# supply_unit.net
KiCad netlist of a schematic drawn in Altium Designer
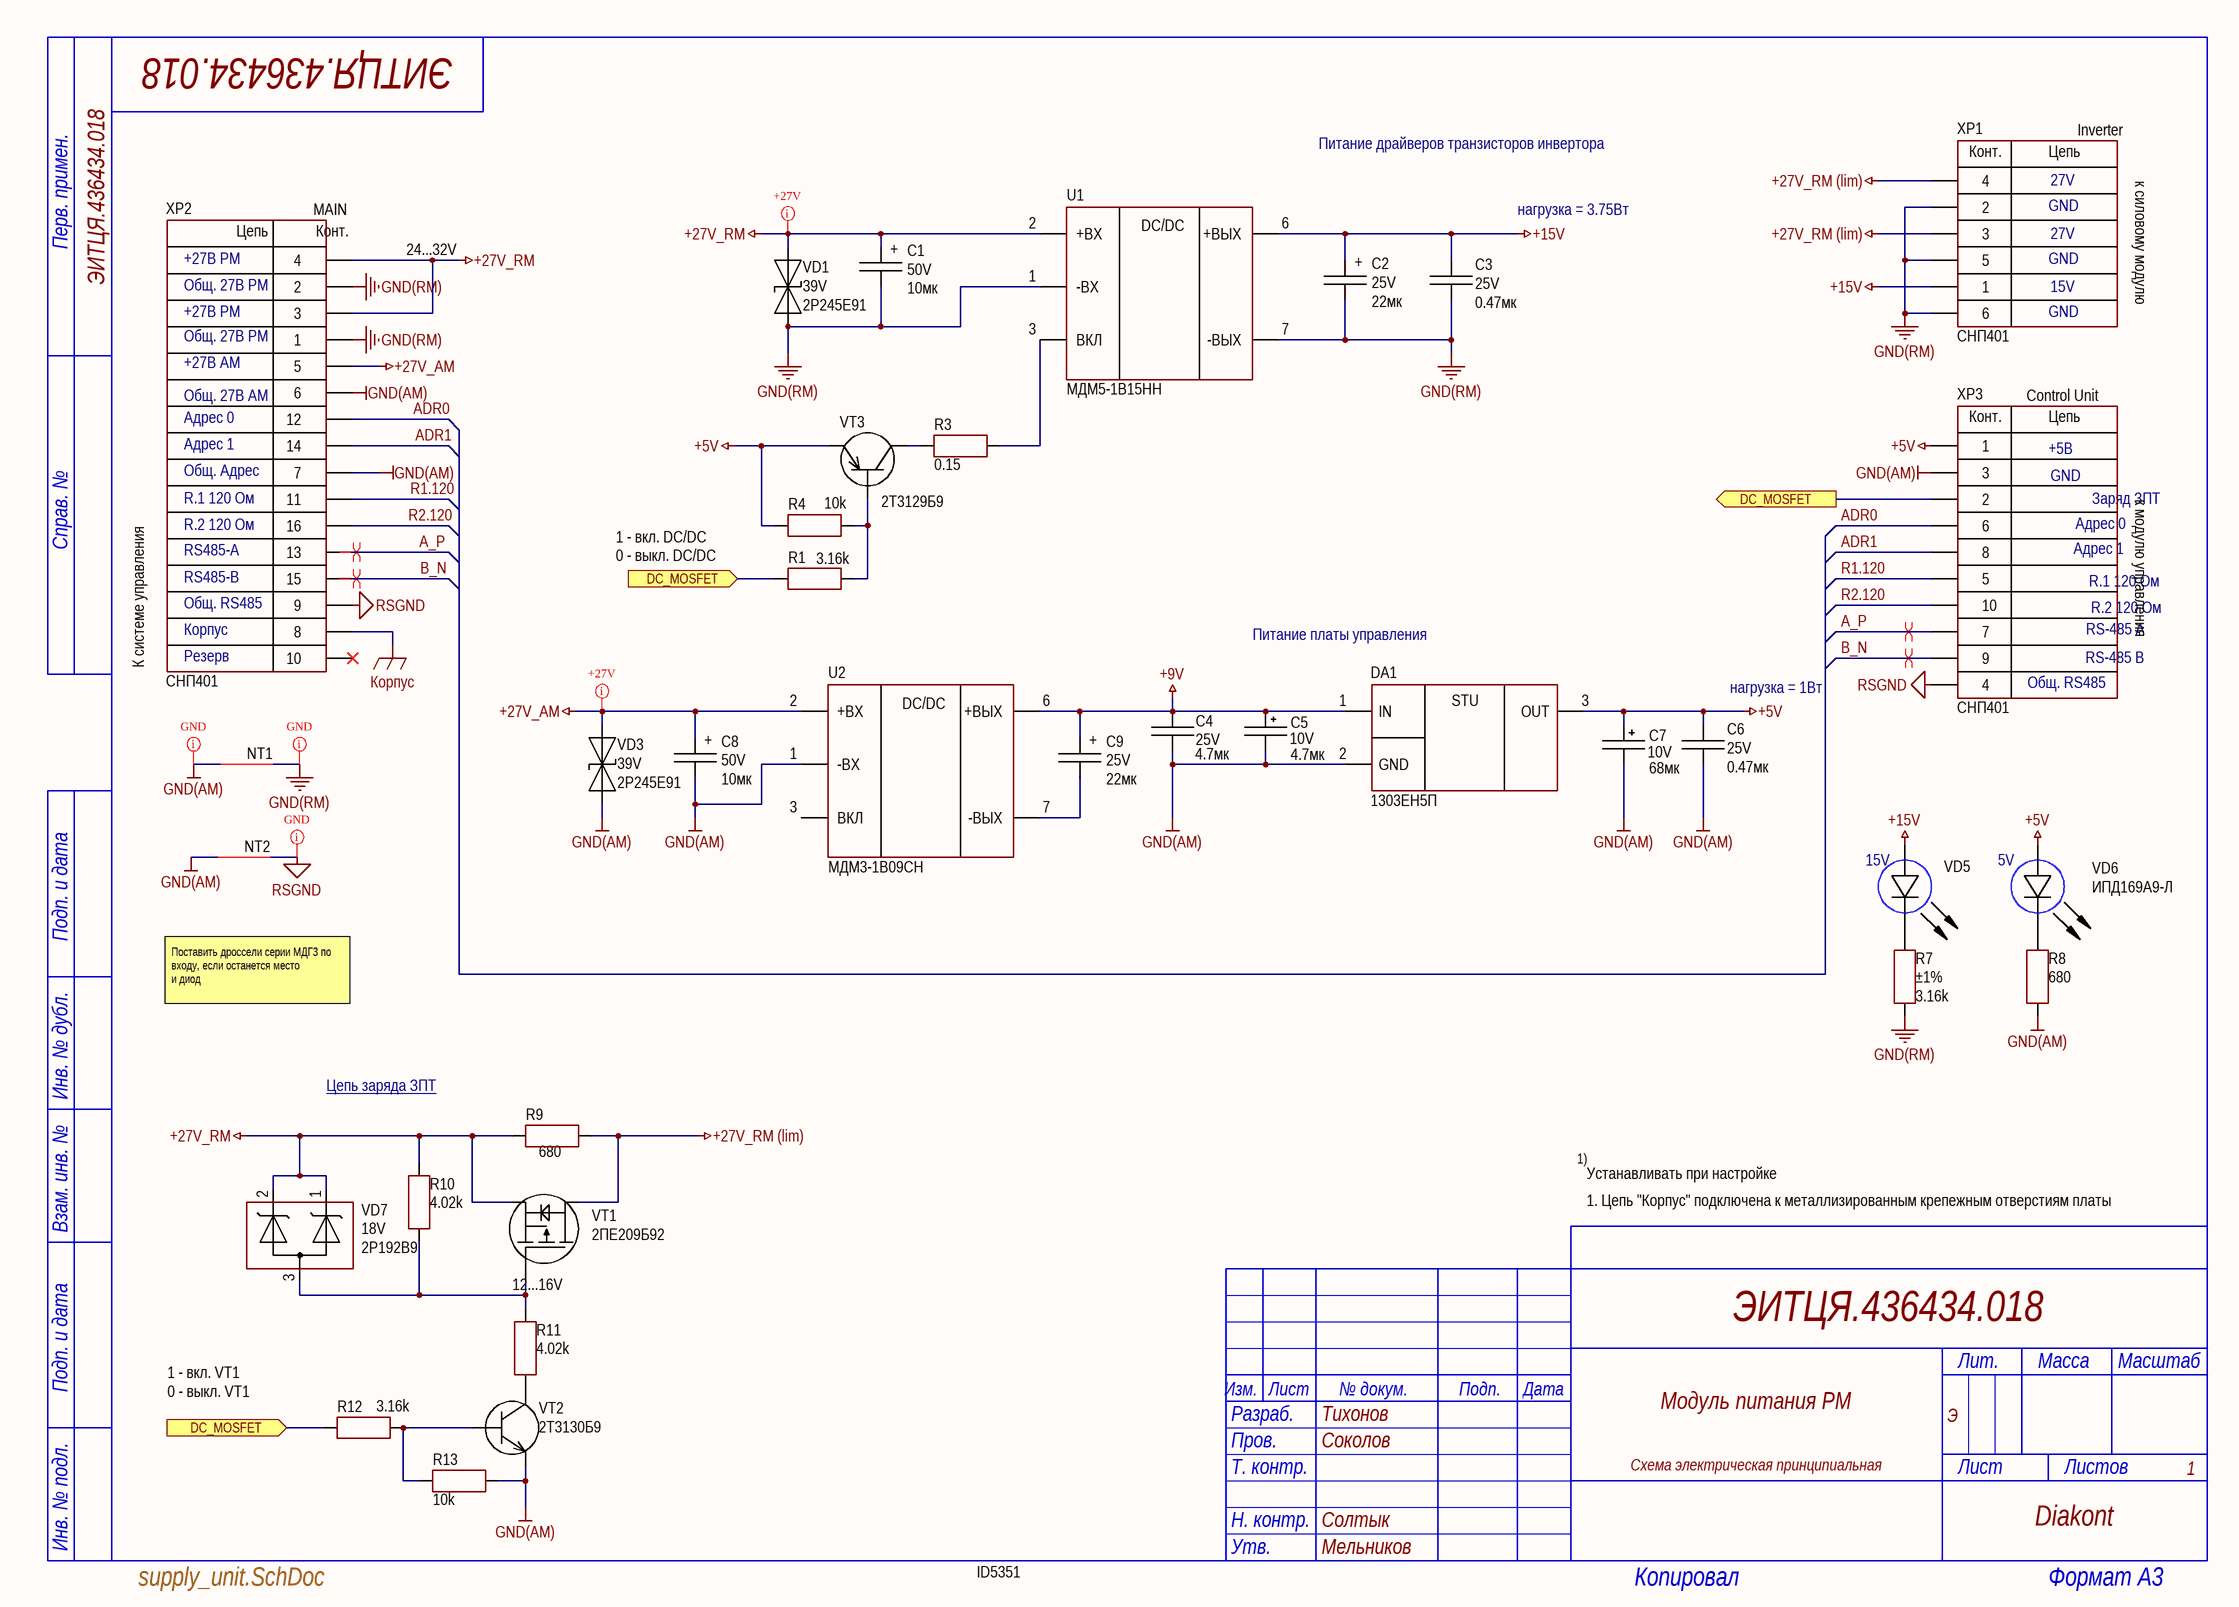
[diagram p0: supply_unit.SchDoc]

(export (version "E")
  (design (tool "Eeschema 10.0.6"))
  (components
    (comp (ref "C1")
      (value "10мк")
      (footprint "StandardCase:CAP: TANTAL-E")
      (fields
        (field (name "MANUFACTURER") "Элеконд")
        (field (name "PARTNUMBER") "К53-68 \"E\"-50 В-10мкф ±10%")
        (field (name "VALUEMANUFACTURERPARTNUMBER") "Tantalum capacitor, 10мк, 50V, ±10%, 0.7 Ом, case E, -60...+125°C")
        (field (name "POLARITY") "+")
        (field (name "VOLTAGE") "50V")
      )
      (libsource (lib "Capacitor") (part "Tantal_E"))
    )
    (comp (ref "C2")
      (value "22мк")
      (footprint "StandardCase:CAP: TANTAL-D")
      (fields
        (field (name "MANUFACTURER") "Элеконд")
        (field (name "PARTNUMBER") "К53-68 \"D\"-25 В-22мкф ±10%")
        (field (name "VALUEMANUFACTURERPARTNUMBER") "Tantalum capacitor, 22мк, 25V, ±10%, 0.7 Ом, case D, -60...+125°C")
        (field (name "POLARITY") "+")
        (field (name "VOLTAGE") "25V")
      )
      (libsource (lib "Capacitor") (part "Tantal_E"))
    )
    (comp (ref "C3")
      (value "0.47мк")
      (footprint "StandardCase:CAP: 1206")
      (fields
        (field (name "MANUFACTURER") "Монолит")
        (field (name "PARTNUMBER") "К10-84в-3216М-25В-0,47 мкФ ±10%-Н90-N-A")
        (field (name "VALUEMANUFACTURERPARTNUMBER") "Ceramic capacitor, 0.47мк, Н90, ±10%, 25V, 1206 (3216M), ")
        (field (name "VOLTAGE") "25V")
      )
      (libsource (lib "Capacitor") (part "Ceramic_0603"))
    )
    (comp (ref "C4")
      (value "4.7мк")
      (footprint "StandardCase:CAP: 1812")
      (fields
        (field (name "MANUFACTURER") "Монолит")
        (field (name "PARTNUMBER") "К10-84в-4532М-25В-4,7 мкФ +80/-20%-Н90-N-A")
        (field (name "VALUEMANUFACTURERPARTNUMBER") "Ceramic capacitor, 4.7мк, H90, +80 -20%, 25V, 1812 (4532М) (4.5x3.2), -55...+125°C")
        (field (name "VOLTAGE") "25V")
      )
      (libsource (lib "Capacitor") (part "Ceramic_1812"))
    )
    (comp (ref "C5")
      (value "4.7мк")
      (footprint "StandardCase:CAP: TANTAL-A")
      (fields
        (field (name "MANUFACTURER") "Элеконд")
        (field (name "PARTNUMBER") "К53-68 \"А\"-10 В-4.7 мкф")
        (field (name "VALUEMANUFACTURERPARTNUMBER") "Tantalum capacitor, 4.7мк, 10V, ±10%, 2Ohm, case A (3216), -55...+125°C")
        (field (name "VOLTAGE") "10V")
      )
      (libsource (lib "Capacitor") (part "Tantal_A"))
    )
    (comp (ref "C6")
      (value "0.47мк")
      (footprint "StandardCase:CAP: 1206")
      (fields
        (field (name "MANUFACTURER") "Монолит")
        (field (name "PARTNUMBER") "К10-84в-3216М-25В-0,47 мкФ ±10%-Н90-N-A")
        (field (name "VALUEMANUFACTURERPARTNUMBER") "Ceramic capacitor, 0.47мк, Н90, ±10%, 25V, 1206 (3216M), ")
        (field (name "VOLTAGE") "25V")
      )
      (libsource (lib "Capacitor") (part "Ceramic_0603"))
    )
    (comp (ref "C7")
      (value "68мк")
      (footprint "StandardCase:CAP: TANTAL-C")
      (fields
        (field (name "MANUFACTURER") "Элеконд")
        (field (name "PARTNUMBER") "К53-68 \"C\"-10 В-68 мкф")
        (field (name "VALUEMANUFACTURERPARTNUMBER") "Tantalum capacitor, 68мк, 10V, ±10%, 1.2 - 1.8Ohm, case C, -55...+125°C")
        (field (name "VOLTAGE") "10V")
      )
      (libsource (lib "Capacitor") (part "Tantal_A"))
    )
    (comp (ref "C8")
      (value "10мк")
      (footprint "StandardCase:CAP: TANTAL-E")
      (fields
        (field (name "MANUFACTURER") "Элеконд")
        (field (name "PARTNUMBER") "К53-68 \"E\"-50 В-10мкф ±10%")
        (field (name "VALUEMANUFACTURERPARTNUMBER") "Tantalum capacitor, 10мк, 50V, ±10%, 0.7 Ом, case E, -60...+125°C")
        (field (name "POLARITY") "+")
        (field (name "VOLTAGE") "50V")
      )
      (libsource (lib "Capacitor") (part "Tantal_E"))
    )
    (comp (ref "C9")
      (value "22мк")
      (footprint "StandardCase:CAP: TANTAL-D")
      (fields
        (field (name "MANUFACTURER") "Элеконд")
        (field (name "PARTNUMBER") "К53-68 \"D\"-25 В-22мкф ±10%")
        (field (name "VALUEMANUFACTURERPARTNUMBER") "Tantalum capacitor, 22мк, 25V, ±10%, 0.7 Ом, case D, -60...+125°C")
        (field (name "POLARITY") "+")
        (field (name "VOLTAGE") "25V")
      )
      (libsource (lib "Capacitor") (part "Tantal_E"))
    )
    (comp (ref "DA1")
      (value "~")
      (footprint "TO220 (КТ-28А)")
      (description "Linear voltage regulator 5V")
      (fields
        (field (name "MANUFACTURER") "ELTOM")
        (field (name "VALUEMANUFACTURERPARTNUMBER") "Linear voltage regulator, input 5.8...16V, 0.6V, output 5V, 5A, -60...+125°C, КТ28А (TO-220)")
        (field (name "PARTNUMBER") "1303ЕН5П")
      )
      (libsource (lib "IC. Power supply") (part "1303ЕН5П"))
    )
    (comp (ref "NT1")
      (value "~")
      (footprint "CustomCase:NetTie_0603")
      (libsource (lib "Connector") (part "NetTie"))
    )
    (comp (ref "NT2")
      (value "~")
      (footprint "CustomCase:NetTie_0603")
      (libsource (lib "Connector") (part "NetTie"))
    )
    (comp (ref "R1")
      (value "3.16k")
      (footprint "RES: 0603P")
      (fields
        (field (name "MANUFACTURER") "ОАО Ресурс")
        (field (name "PARTNUMBER") "Р1-12-0,1ум.-3.16~кОм ±1%-М ШКАБ.434110.002 ТУ")
        (field (name "VALUEMANUFACTURERPARTNUMBER") "Resistor film, 3.16k, ±1%, 0603, 0.1W, -55...+125°C")
      )
      (libsource (lib "") (part "Resistor_0603_1"))
    )
    (comp (ref "R3")
      (value "0.15")
      (footprint "RES: 0603P")
      (fields
        (field (name "MANUFACTURER") "ОАО Ресурс")
        (field (name "PARTNUMBER") "Р1-12-0,1ум.-0.15~Ом ±20%-М ШКАБ.434110.002 ТУ")
        (field (name "VALUEMANUFACTURERPARTNUMBER") "Resistor film, 0.15, ±20%, 0603, 0.1W, -55...+125°C")
      )
      (libsource (lib "Resistor") (part "Resistor_0603"))
    )
    (comp (ref "R4")
      (value "10k")
      (footprint "RES: 0603P")
      (fields
        (field (name "MANUFACTURER") "ОАО Ресурс")
        (field (name "PARTNUMBER") "Р1-12-0,1ум.-10~кОм ±5%-М ШКАБ.434110.002 ТУ")
        (field (name "VALUEMANUFACTURERPARTNUMBER") "Resistor film, 10k, ±5%, 0603, 0.1W, -55...+125°C")
      )
      (libsource (lib "") (part "Resistor_0603_2"))
    )
    (comp (ref "R7")
      (value "3.16k")
      (footprint "RES: 0603P")
      (fields
        (field (name "MANUFACTURER") "ОАО Ресурс")
        (field (name "PARTNUMBER") "Р1-12-0,1ум.-3.16~кОм ±1%-М ШКАБ.434110.002 ТУ")
        (field (name "VALUEMANUFACTURERPARTNUMBER") "Resistor film, 3.16k, ±1%, 0603, 0.1W, -55...+125°C")
        (field (name "TOLERANCE") "±1%")
      )
      (libsource (lib "") (part "Resistor_0603_2"))
    )
    (comp (ref "R8")
      (value "680")
      (footprint "RES: 0603P")
      (fields
        (field (name "MANUFACTURER") "ОАО Ресурс")
        (field (name "PARTNUMBER") "Р1-12-0,1ум.-680~Ом ±5%-М ШКАБ.434110.002 ТУ")
        (field (name "VALUEMANUFACTURERPARTNUMBER") "Resistor film, 680, ±5%, 0603, 0.1W, -55...+125°C")
      )
      (libsource (lib "") (part "Resistor_0603_1"))
    )
    (comp (ref "R9")
      (value "680")
      (footprint "StandardCase:RES: 0805P")
      (fields
        (field (name "MANUFACTURER") "Ресурс")
        (field (name "PARTNUMBER") "Р1-12-0,125-680 Ом ±5%-М ШКАБ.434110.002 ТУ")
        (field (name "VALUEMANUFACTURERPARTNUMBER") "Resistor film, 680, ±5%, 0805, 0.125W, ")
      )
      (libsource (lib "Resistor") (part "Resistor_0805"))
    )
    (comp (ref "R10")
      (value "4.02k")
      (footprint "RES: 0805P")
      (fields
        (field (name "MANUFACTURER") "ОАО Ресурс")
        (field (name "PARTNUMBER") "Р1-12-0,1ум.-4.02~кОм ±1%-М ШКАБ.434110.002 ТУ")
        (field (name "VALUEMANUFACTURERPARTNUMBER") "Resistor film, 4.02k, ±1%, 0805, 0.125W, -55...+125°C")
      )
      (libsource (lib "") (part "Resistor_0603_1"))
    )
    (comp (ref "R11")
      (value "4.02k")
      (footprint "RES: 0805P")
      (fields
        (field (name "MANUFACTURER") "ОАО Ресурс")
        (field (name "PARTNUMBER") "Р1-12-0,1ум.-4.02~кОм ±1%-М ШКАБ.434110.002 ТУ")
        (field (name "VALUEMANUFACTURERPARTNUMBER") "Resistor film, 4.02k, ±1%, 0805, 0.125W, -55...+125°C")
      )
      (libsource (lib "") (part "Resistor_0603_1"))
    )
    (comp (ref "R12")
      (value "3.16k")
      (footprint "RES: 0603P")
      (fields
        (field (name "MANUFACTURER") "ОАО Ресурс")
        (field (name "PARTNUMBER") "Р1-12-0,1ум.-3.16~кОм ±1%-М ШКАБ.434110.002 ТУ")
        (field (name "VALUEMANUFACTURERPARTNUMBER") "Resistor film, 3.16k, ±1%, 0603, 0.1W, -55...+125°C")
      )
      (libsource (lib "Resistor") (part "Resistor_0603"))
    )
    (comp (ref "R13")
      (value "10k")
      (footprint "RES: 0603P")
      (fields
        (field (name "MANUFACTURER") "ОАО Ресурс")
        (field (name "PARTNUMBER") "Р1-12-0,1ум.-10~кОм ±5%-М ШКАБ.434110.002 ТУ")
        (field (name "VALUEMANUFACTURERPARTNUMBER") "Resistor film, 10k, ±5%, 0603, 0.1W, -55...+125°C")
      )
      (libsource (lib "") (part "Resistor_0603_3"))
    )
    (comp (ref "U1")
      (value "~")
      (footprint "StandardCase:SIP-8")
      (description "DC/DC converter")
      (fields
        (field (name "MANUFACTURER") "Aedon")
        (field (name "VALUEMANUFACTURERPARTNUMBER") "DC/DC converter, isolator, 15V 1.5A, -40...+105°C, SIP-8")
        (field (name "PARTNUMBER") "МДМ5-1В15НН")
      )
      (libsource (lib "Module") (part "МДМ3-1В09СН"))
    )
    (comp (ref "U2")
      (value "~")
      (footprint "StandardCase:SIP-8")
      (description "DC/DC converter")
      (fields
        (field (name "MANUFACTURER") "Aedon")
        (field (name "VALUEMANUFACTURERPARTNUMBER") "DC/DC converter, isolator, 9V 900mA, -40...+105°C, SIP-8")
        (field (name "PARTNUMBER") "МДМ3-1В09СН")
      )
      (libsource (lib "Module") (part "МДМ3-1В09СН"))
    )
    (comp (ref "VD1")
      (value "~")
      (footprint "StandardCase:DIODE: SMB")
      (fields
        (field (name "MANUFACTURER") "НЗПП")
        (field (name "VALUEMANUFACTURERPARTNUMBER") "Zener diode, 39V, 8A, 0.9V, , SMB(КД-42), ")
        (field (name "VOLTAGE") "39V")
        (field (name "PARTNUMBER") "2Р245Е91")
      )
      (libsource (lib "Diode") (part "TVS_single"))
    )
    (comp (ref "VD3")
      (value "~")
      (footprint "StandardCase:DIODE: SMB")
      (fields
        (field (name "MANUFACTURER") "НЗПП")
        (field (name "VALUEMANUFACTURERPARTNUMBER") "Zener diode, 39V, 8A, 0.9V, , SMB(КД-42), ")
        (field (name "VOLTAGE") "39V")
        (field (name "PARTNUMBER") "2Р245Е91")
      )
      (libsource (lib "Diode") (part "TVS_single"))
    )
    (comp (ref "VD5")
      (value "~")
      (footprint "StandardCase:LED: 0603G")
      (fields
        (field (name "MANUFACTURER") "Протон")
        (field (name "VALUEMANUFACTURERPARTNUMBER") "LED, 20mA max, 2.1V typ, 1608, -55...+150°C")
        (field (name "PARTNUMBER") "ИПД169А9-Л")
        (field (name "COMMENTTEXT") "15V")
      )
      (libsource (lib "Diode") (part "LED_single"))
    )
    (comp (ref "VD6")
      (value "~")
      (footprint "StandardCase:LED: 0603G")
      (fields
        (field (name "MANUFACTURER") "Протон")
        (field (name "VALUEMANUFACTURERPARTNUMBER") "LED, 20mA max, 2.1V typ, 1608, -55...+150°C")
        (field (name "PARTNUMBER") "ИПД169А9-Л")
        (field (name "COMMENTTEXT") "5V")
      )
      (libsource (lib "Diode") (part "LED_single"))
    )
    (comp (ref "VD7")
      (value "~")
      (footprint "StandardCase:SOT23")
      (fields
        (field (name "MANUFACTURER") "КРИП")
        (field (name "VALUEMANUFACTURERPARTNUMBER") "TVS diode, 18V, 1A, , , SOT-23, -55...+150°C")
        (field (name "VOLTAGE") "18V")
        (field (name "PARTNUMBER") "2Р192В9")
      )
      (libsource (lib "Diode") (part "TVS_array_var2"))
    )
    (comp (ref "VT1")
      (value "~")
      (footprint "StandardCase:DPAK")
      (fields (field (name "MANUFACTURER") "Ангстрем") (field (name "PARTNUMBER") "2ПЕ209Б92"))
      (libsource (lib "Transistor") (part "MOSFET_P_132"))
    )
    (comp (ref "VT2")
      (value "~")
      (footprint "SOT23")
      (fields
        (field (name "MANUFACTURER") "ООО НПК Далекс")
        (field (name "VALUEMANUFACTURERPARTNUMBER") "NPN transistor, 30V, 100mA, , 300mW, 0.7V, 500, SOT-23 (КТ-46), -55...+125°C")
        (field (name "PARTNUMBER") "2Т3130Б9")
      )
      (libsource (lib "Transistor") (part "BJT_NPN_132"))
    )
    (comp (ref "VT3")
      (value "~")
      (footprint "StandardCase:SOT23")
      (fields
        (field (name "VALUEMANUFACTURERPARTNUMBER") "NPN transistor, 40V, 100mA, , 200mW, 1.3V, 220, SOT-23 (КТ-46), ")
        (field (name "PARTNUMBER") "2Т3129Б9")
      )
      (libsource (lib "Transistor") (part "BJT_PNP_123"))
    )
    (comp (ref "XP1")
      (value "~")
      (footprint "CON: M80-5000605")
      (description "вилка на плату")
      (fields
        (field (name "MANUFACTURER") "Электроделать")
        (field (name "VALUEMANUFACTURERPARTNUMBER") "Вилка, 6pin, 2mm, 120VAC, 1.5A")
        (field (name "COMMENTTEXT") "СНП401")
      )
      (libsource (lib "Connector") (part "M80-5000605 Harwin"))
    )
    (comp (ref "XP2")
      (value "~")
      (footprint "CustomCase:CON: M80-5001605")
      (description "вилка на плату")
      (fields
        (field (name "MANUFACTURER") "Электродеталь")
        (field (name "VALUEMANUFACTURERPARTNUMBER") ", 16pin, 2mm, 120VAC, 1.5A")
        (field (name "COMMENTTEXT") "СНП401")
      )
      (libsource (lib "Connector") (part "M80-5001205 Harwin_1"))
    )
    (comp (ref "XP3")
      (value "~")
      (footprint "CON: M80-5001005")
      (description "вилка на плату")
      (fields
        (field (name "MANUFACTURER") "Электродеталь")
        (field (name "VALUEMANUFACTURERPARTNUMBER") "Вилка, 10pin, 2mm, 100V, 1.5A")
        (field (name "COMMENTTEXT") "СНП401")
      )
      (libsource (lib "Connector") (part "M80-5001005 Harwin"))
    )
  )
  (nets
    (net (code "1") (name "+5V") (class "Default")
      (node (ref "C6") (pin "2") (pinfunction "2_2") (pintype "passive"))
      (node (ref "C7") (pin "1") (pinfunction "1_1") (pintype "power_in"))
      (node (ref "DA1") (pin "3") (pinfunction "OUT_3") (pintype "power_in"))
      (node (ref "R4") (pin "1") (pinfunction "1_1") (pintype "passive"))
      (node (ref "VD6") (pin "1") (pinfunction "A_1") (pintype "passive"))
      (node (ref "VT3") (pin "2") (pinfunction "E_2") (pintype "passive"))
      (node (ref "XP3") (pin "1") (pinfunction "1_1") (pintype "passive"))
    )
    (net (code "2") (name "+9V") (class "Default")
      (node (ref "C4") (pin "2") (pinfunction "2_2") (pintype "passive"))
      (node (ref "C5") (pin "1") (pinfunction "1_1") (pintype "power_in"))
      (node (ref "C9") (pin "2") (pinfunction "2_2") (pintype "power_in"))
      (node (ref "DA1") (pin "1") (pinfunction "IN_1") (pintype "power_in"))
      (node (ref "U2") (pin "6") (pinfunction "+ВЫХ_6") (pintype "power_in"))
    )
    (net (code "3") (name "+15V") (class "Default")
      (node (ref "C2") (pin "2") (pinfunction "2_2") (pintype "power_in"))
      (node (ref "C3") (pin "2") (pinfunction "2_2") (pintype "passive"))
      (node (ref "U1") (pin "6") (pinfunction "+ВЫХ_6") (pintype "power_in"))
      (node (ref "VD5") (pin "1") (pinfunction "A_1") (pintype "passive"))
      (node (ref "XP1") (pin "1") (pinfunction "1_1") (pintype "passive"))
    )
    (net (code "4") (name "+27V_AM") (class "Default")
      (node (ref "C8") (pin "2") (pinfunction "2_2") (pintype "power_in"))
      (node (ref "U2") (pin "2") (pinfunction "+ВХ_2") (pintype "power_in"))
      (node (ref "VD3") (pin "2") (pinfunction "C_2") (pintype "passive"))
      (node (ref "XP2") (pin "5") (pinfunction "5_5") (pintype "passive"))
    )
    (net (code "5") (name "+27V_RM") (class "Default")
      (node (ref "C1") (pin "2") (pinfunction "2_2") (pintype "power_in"))
      (node (ref "R10") (pin "1") (pinfunction "1_1") (pintype "passive"))
      (node (ref "R9") (pin "1") (pinfunction "1_1") (pintype "passive"))
      (node (ref "U1") (pin "2") (pinfunction "+ВХ_2") (pintype "power_in"))
      (node (ref "VD1") (pin "2") (pinfunction "C_2") (pintype "passive"))
      (node (ref "VD7") (pin "1") (pinfunction "K1_1") (pintype "passive"))
      (node (ref "VD7") (pin "2") (pinfunction "K2_2") (pintype "passive"))
      (node (ref "VT1") (pin "2") (pinfunction "S_2") (pintype "passive"))
      (node (ref "XP2") (pin "3") (pinfunction "3_3") (pintype "passive"))
      (node (ref "XP2") (pin "4") (pinfunction "4_4") (pintype "passive"))
    )
    (net (code "6") (name "+27V_RM (lim)") (class "Default")
      (node (ref "R9") (pin "2") (pinfunction "2_2") (pintype "passive"))
      (node (ref "VT1") (pin "3") (pinfunction "D_3") (pintype "passive"))
      (node (ref "XP1") (pin "3") (pinfunction "3_3") (pintype "passive"))
      (node (ref "XP1") (pin "4") (pinfunction "4_4") (pintype "passive"))
    )
    (net (code "7") (name "/ADR0") (class "Default")
      (node (ref "XP2") (pin "12") (pinfunction "12_12") (pintype "passive"))
      (node (ref "XP3") (pin "6") (pinfunction "6_6") (pintype "passive"))
    )
    (net (code "8") (name "/ADR1") (class "Default")
      (node (ref "XP2") (pin "14") (pinfunction "14_14") (pintype "passive"))
      (node (ref "XP3") (pin "8") (pinfunction "8_8") (pintype "passive"))
    )
    (net (code "9") (name "/A_P") (class "Default")
      (node (ref "XP2") (pin "13") (pinfunction "13_13") (pintype "passive"))
      (node (ref "XP3") (pin "7") (pinfunction "7_7") (pintype "passive"))
    )
    (net (code "10") (name "/B_N") (class "Default")
      (node (ref "XP2") (pin "15") (pinfunction "15_15") (pintype "passive"))
      (node (ref "XP3") (pin "9") (pinfunction "9_9") (pintype "passive"))
    )
    (net (code "11") (name "/DC_MOSFET") (class "Default")
      (node (ref "R1") (pin "2") (pinfunction "2_2") (pintype "passive"))
      (node (ref "R12") (pin "1") (pinfunction "1_1") (pintype "passive"))
      (node (ref "XP3") (pin "2") (pinfunction "2_2") (pintype "passive"))
    )
    (net (code "12") (name "/R1.120") (class "Default")
      (node (ref "XP2") (pin "11") (pinfunction "11_11") (pintype "passive"))
      (node (ref "XP3") (pin "5") (pinfunction "5_5") (pintype "passive"))
    )
    (net (code "13") (name "/R2.120") (class "Default")
      (node (ref "XP2") (pin "16") (pinfunction "16_16") (pintype "passive"))
      (node (ref "XP3") (pin "10") (pinfunction "10_10") (pintype "passive"))
    )
    (net (code "14") (name "GND(AM)") (class "Default")
      (node (ref "C4") (pin "1") (pinfunction "1_1") (pintype "passive"))
      (node (ref "C5") (pin "2") (pinfunction "2_2") (pintype "power_in"))
      (node (ref "C6") (pin "1") (pinfunction "1_1") (pintype "passive"))
      (node (ref "C7") (pin "2") (pinfunction "2_2") (pintype "power_in"))
      (node (ref "C8") (pin "1") (pinfunction "1_1") (pintype "power_in"))
      (node (ref "DA1") (pin "2") (pinfunction "GND_2") (pintype "power_in"))
      (node (ref "NT1") (pin "1") (pinfunction "1_1") (pintype "passive"))
      (node (ref "NT2") (pin "1") (pinfunction "1_1") (pintype "passive"))
      (node (ref "R13") (pin "1") (pinfunction "1_1") (pintype "passive"))
      (node (ref "R8") (pin "2") (pinfunction "2_2") (pintype "passive"))
      (node (ref "U2") (pin "1") (pinfunction "-ВХ_1") (pintype "power_in"))
      (node (ref "VD3") (pin "1") (pinfunction "A_1") (pintype "passive"))
      (node (ref "VT2") (pin "2") (pinfunction "E_2") (pintype "passive"))
      (node (ref "XP2") (pin "6") (pinfunction "6_6") (pintype "passive"))
      (node (ref "XP2") (pin "7") (pinfunction "7_7") (pintype "passive"))
      (node (ref "XP3") (pin "3") (pinfunction "3_3") (pintype "passive"))
    )
    (net (code "15") (name "GND(RM)") (class "Default")
      (node (ref "C1") (pin "1") (pinfunction "1_1") (pintype "power_in"))
      (node (ref "C2") (pin "1") (pinfunction "1_1") (pintype "power_in"))
      (node (ref "C3") (pin "1") (pinfunction "1_1") (pintype "passive"))
      (node (ref "NT1") (pin "2") (pinfunction "2_2") (pintype "passive"))
      (node (ref "R7") (pin "1") (pinfunction "1_1") (pintype "passive"))
      (node (ref "U1") (pin "1") (pinfunction "-ВХ_1") (pintype "power_in"))
      (node (ref "U1") (pin "7") (pinfunction "-ВЫХ_7") (pintype "power_in"))
      (node (ref "VD1") (pin "1") (pinfunction "A_1") (pintype "passive"))
      (node (ref "XP1") (pin "2") (pinfunction "2_2") (pintype "passive"))
      (node (ref "XP1") (pin "5") (pinfunction "5_5") (pintype "passive"))
      (node (ref "XP1") (pin "6") (pinfunction "6_6") (pintype "passive"))
      (node (ref "XP2") (pin "1") (pinfunction "1_1") (pintype "passive"))
      (node (ref "XP2") (pin "2") (pinfunction "2_2") (pintype "passive"))
    )
    (net (code "16") (name "Net-(U1-ВКЛ)") (class "Default")
      (node (ref "R3") (pin "2") (pinfunction "2_2") (pintype "passive"))
      (node (ref "U1") (pin "3") (pinfunction "ВКЛ_3") (pintype "power_in"))
    )
    (net (code "17") (name "Net-(U2--ВЫХ)") (class "Default")
      (node (ref "C9") (pin "1") (pinfunction "1_1") (pintype "power_in"))
      (node (ref "U2") (pin "7") (pinfunction "-ВЫХ_7") (pintype "power_in"))
    )
    (net (code "18") (name "Net-(VD5-C)") (class "Default")
      (node (ref "R7") (pin "2") (pinfunction "2_2") (pintype "passive"))
      (node (ref "VD5") (pin "2") (pinfunction "C_2") (pintype "passive"))
    )
    (net (code "19") (name "Net-(VD6-C)") (class "Default")
      (node (ref "R8") (pin "1") (pinfunction "1_1") (pintype "passive"))
      (node (ref "VD6") (pin "2") (pinfunction "C_2") (pintype "passive"))
    )
    (net (code "20") (name "Net-(VD7-A)") (class "Default")
      (node (ref "R10") (pin "2") (pinfunction "2_2") (pintype "passive"))
      (node (ref "R11") (pin "1") (pinfunction "1_1") (pintype "passive"))
      (node (ref "VD7") (pin "3") (pinfunction "A_3") (pintype "passive"))
      (node (ref "VT1") (pin "1") (pinfunction "G_1") (pintype "passive"))
    )
    (net (code "21") (name "Net-(VT2-B)") (class "Default")
      (node (ref "R12") (pin "2") (pinfunction "2_2") (pintype "passive"))
      (node (ref "R13") (pin "2") (pinfunction "2_2") (pintype "passive"))
      (node (ref "VT2") (pin "1") (pinfunction "B_1") (pintype "passive"))
    )
    (net (code "22") (name "Net-(VT2-C)") (class "Default")
      (node (ref "R11") (pin "2") (pinfunction "2_2") (pintype "passive"))
      (node (ref "VT2") (pin "3") (pinfunction "C_3") (pintype "passive"))
    )
    (net (code "23") (name "Net-(VT3-B)") (class "Default")
      (node (ref "R1") (pin "1") (pinfunction "1_1") (pintype "passive"))
      (node (ref "R4") (pin "2") (pinfunction "2_2") (pintype "passive"))
      (node (ref "VT3") (pin "1") (pinfunction "B_1") (pintype "passive"))
    )
    (net (code "24") (name "Net-(VT3-C)") (class "Default")
      (node (ref "R3") (pin "1") (pinfunction "1_1") (pintype "passive"))
      (node (ref "VT3") (pin "3") (pinfunction "C_3") (pintype "passive"))
    )
    (net (code "25") (name "RSGND") (class "Default")
      (node (ref "NT2") (pin "2") (pinfunction "2_2") (pintype "passive"))
      (node (ref "XP2") (pin "9") (pinfunction "9_9") (pintype "passive"))
      (node (ref "XP3") (pin "4") (pinfunction "4_4") (pintype "passive"))
    )
    (net (code "26") (name "unconnected-(U2-ВКЛ-Pad3)") (class "Default")
      (node (ref "U2") (pin "3") (pinfunction "ВКЛ_3") (pintype "power_in"))
    )
    (net (code "27") (name "unconnected-(XP2-Pad10)") (class "Default")
      (node (ref "XP2") (pin "10") (pinfunction "10_10") (pintype "passive+no_connect"))
    )
    (net (code "28") (name "Корпус") (class "Default")
      (node (ref "XP2") (pin "8") (pinfunction "8_8") (pintype "passive"))
    )
  )
)
